# Top.net
KiCad netlist of a schematic drawn in Altium Designer
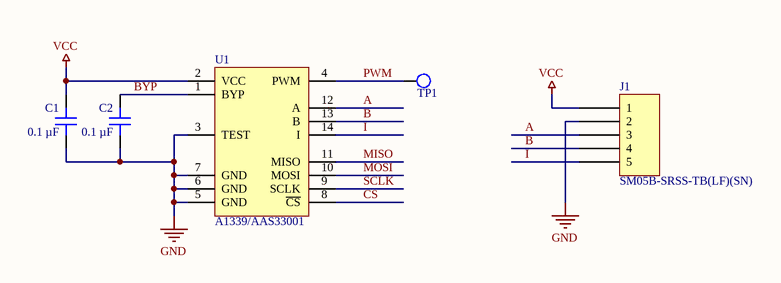
[diagram p0: Top.SchDoc]

(export (version "E")
  (design (tool "Eeschema 10.0.6"))
  (components
    (comp (ref "C1")
      (value "0.1 µF")
      (footprint "CAP 0402_1005")
      (description "CAP CER 0.1UF 25V X7R 0402")
      (fields (field (name "PART NUMBER") "C0402C104K3RAC7867") (field (name "MANUFACTURER") "KEMET"))
      (libsource (lib "Celestial Altium Library - altium_library") (part "Capacitor"))
    )
    (comp (ref "C2")
      (value "0.1 µF")
      (footprint "CAP 0402_1005")
      (description "CAP CER 0.1UF 25V X7R 0402")
      (fields (field (name "PART NUMBER") "C0402C104K3RAC7867") (field (name "MANUFACTURER") "KEMET"))
      (libsource (lib "Celestial Altium Library - altium_library") (part "Capacitor"))
    )
    (comp (ref "J1")
      (value "SM05B-SRSS-TB(LF)(SN)")
      (footprint "JST SM05B-SRSS-TB")
      (description "CONN HEADER SMD R/A 5POS 1MM")
      (fields (field (name "MANUFACTURER") "JST Sales America Inc."))
      (libsource (lib "Celestial Altium Library - altium_library") (part "5 Pin"))
    )
    (comp (ref "TP1")
      (value "0.8mm")
      (footprint "TP  0.8mm")
      (description "Test point")
      (libsource (lib "IC") (part "TP 0.8mm"))
    )
    (comp (ref "U1")
      (value "A1339/AAS33001")
      (footprint "TSSOP14")
      (libsource (lib "IC") (part "A1339/AAS33001"))
    )
  )
  (nets
    (net (code "1") (name "/A") (class "Default")
      (node (ref "J1") (pin "3") (pinfunction "3_3") (pintype "passive"))
      (node (ref "U1") (pin "12") (pinfunction "A_12") (pintype "passive"))
    )
    (net (code "2") (name "/B") (class "Default")
      (node (ref "J1") (pin "4") (pinfunction "4_4") (pintype "passive"))
      (node (ref "U1") (pin "13") (pinfunction "B_13") (pintype "passive"))
    )
    (net (code "3") (name "/BYP") (class "Default")
      (node (ref "C2") (pin "1") (pinfunction "1_1") (pintype "passive"))
      (node (ref "U1") (pin "1") (pinfunction "BYP_1") (pintype "passive"))
    )
    (net (code "4") (name "/I") (class "Default")
      (node (ref "J1") (pin "5") (pinfunction "5_5") (pintype "passive"))
      (node (ref "U1") (pin "14") (pinfunction "I_14") (pintype "passive"))
    )
    (net (code "5") (name "/MISO") (class "Default")
      (node (ref "U1") (pin "11") (pinfunction "MISO_11") (pintype "passive"))
    )
    (net (code "6") (name "/MOSI") (class "Default")
      (node (ref "U1") (pin "10") (pinfunction "MOSI_10") (pintype "passive"))
    )
    (net (code "7") (name "/PWM") (class "Default")
      (node (ref "TP1") (pin "1") (pinfunction "TP_1") (pintype "passive"))
      (node (ref "U1") (pin "4") (pinfunction "PWM_4") (pintype "passive"))
    )
    (net (code "8") (name "/SCLK") (class "Default")
      (node (ref "U1") (pin "9") (pinfunction "SCLK_9") (pintype "passive"))
    )
    (net (code "9") (name "/~{CS}") (class "Default")
      (node (ref "U1") (pin "8") (pinfunction "~{CS}_8") (pintype "passive"))
    )
    (net (code "10") (name "GND") (class "Default")
      (node (ref "C1") (pin "2") (pinfunction "2_2") (pintype "passive"))
      (node (ref "C2") (pin "2") (pinfunction "2_2") (pintype "passive"))
      (node (ref "J1") (pin "2") (pinfunction "2_2") (pintype "passive"))
      (node (ref "U1") (pin "3") (pinfunction "TEST_3") (pintype "passive"))
      (node (ref "U1") (pin "5") (pinfunction "GND_5") (pintype "passive"))
      (node (ref "U1") (pin "6") (pinfunction "GND_6") (pintype "passive"))
      (node (ref "U1") (pin "7") (pinfunction "GND_7") (pintype "passive"))
    )
    (net (code "11") (name "VCC") (class "Default")
      (node (ref "C1") (pin "1") (pinfunction "1_1") (pintype "passive"))
      (node (ref "J1") (pin "1") (pinfunction "1_1") (pintype "passive"))
      (node (ref "U1") (pin "2") (pinfunction "VCC_2") (pintype "passive"))
    )
  )
)
